# DistributedVisionSchematicPage1_33.net
KiCad netlist of a schematic drawn in EAGLE
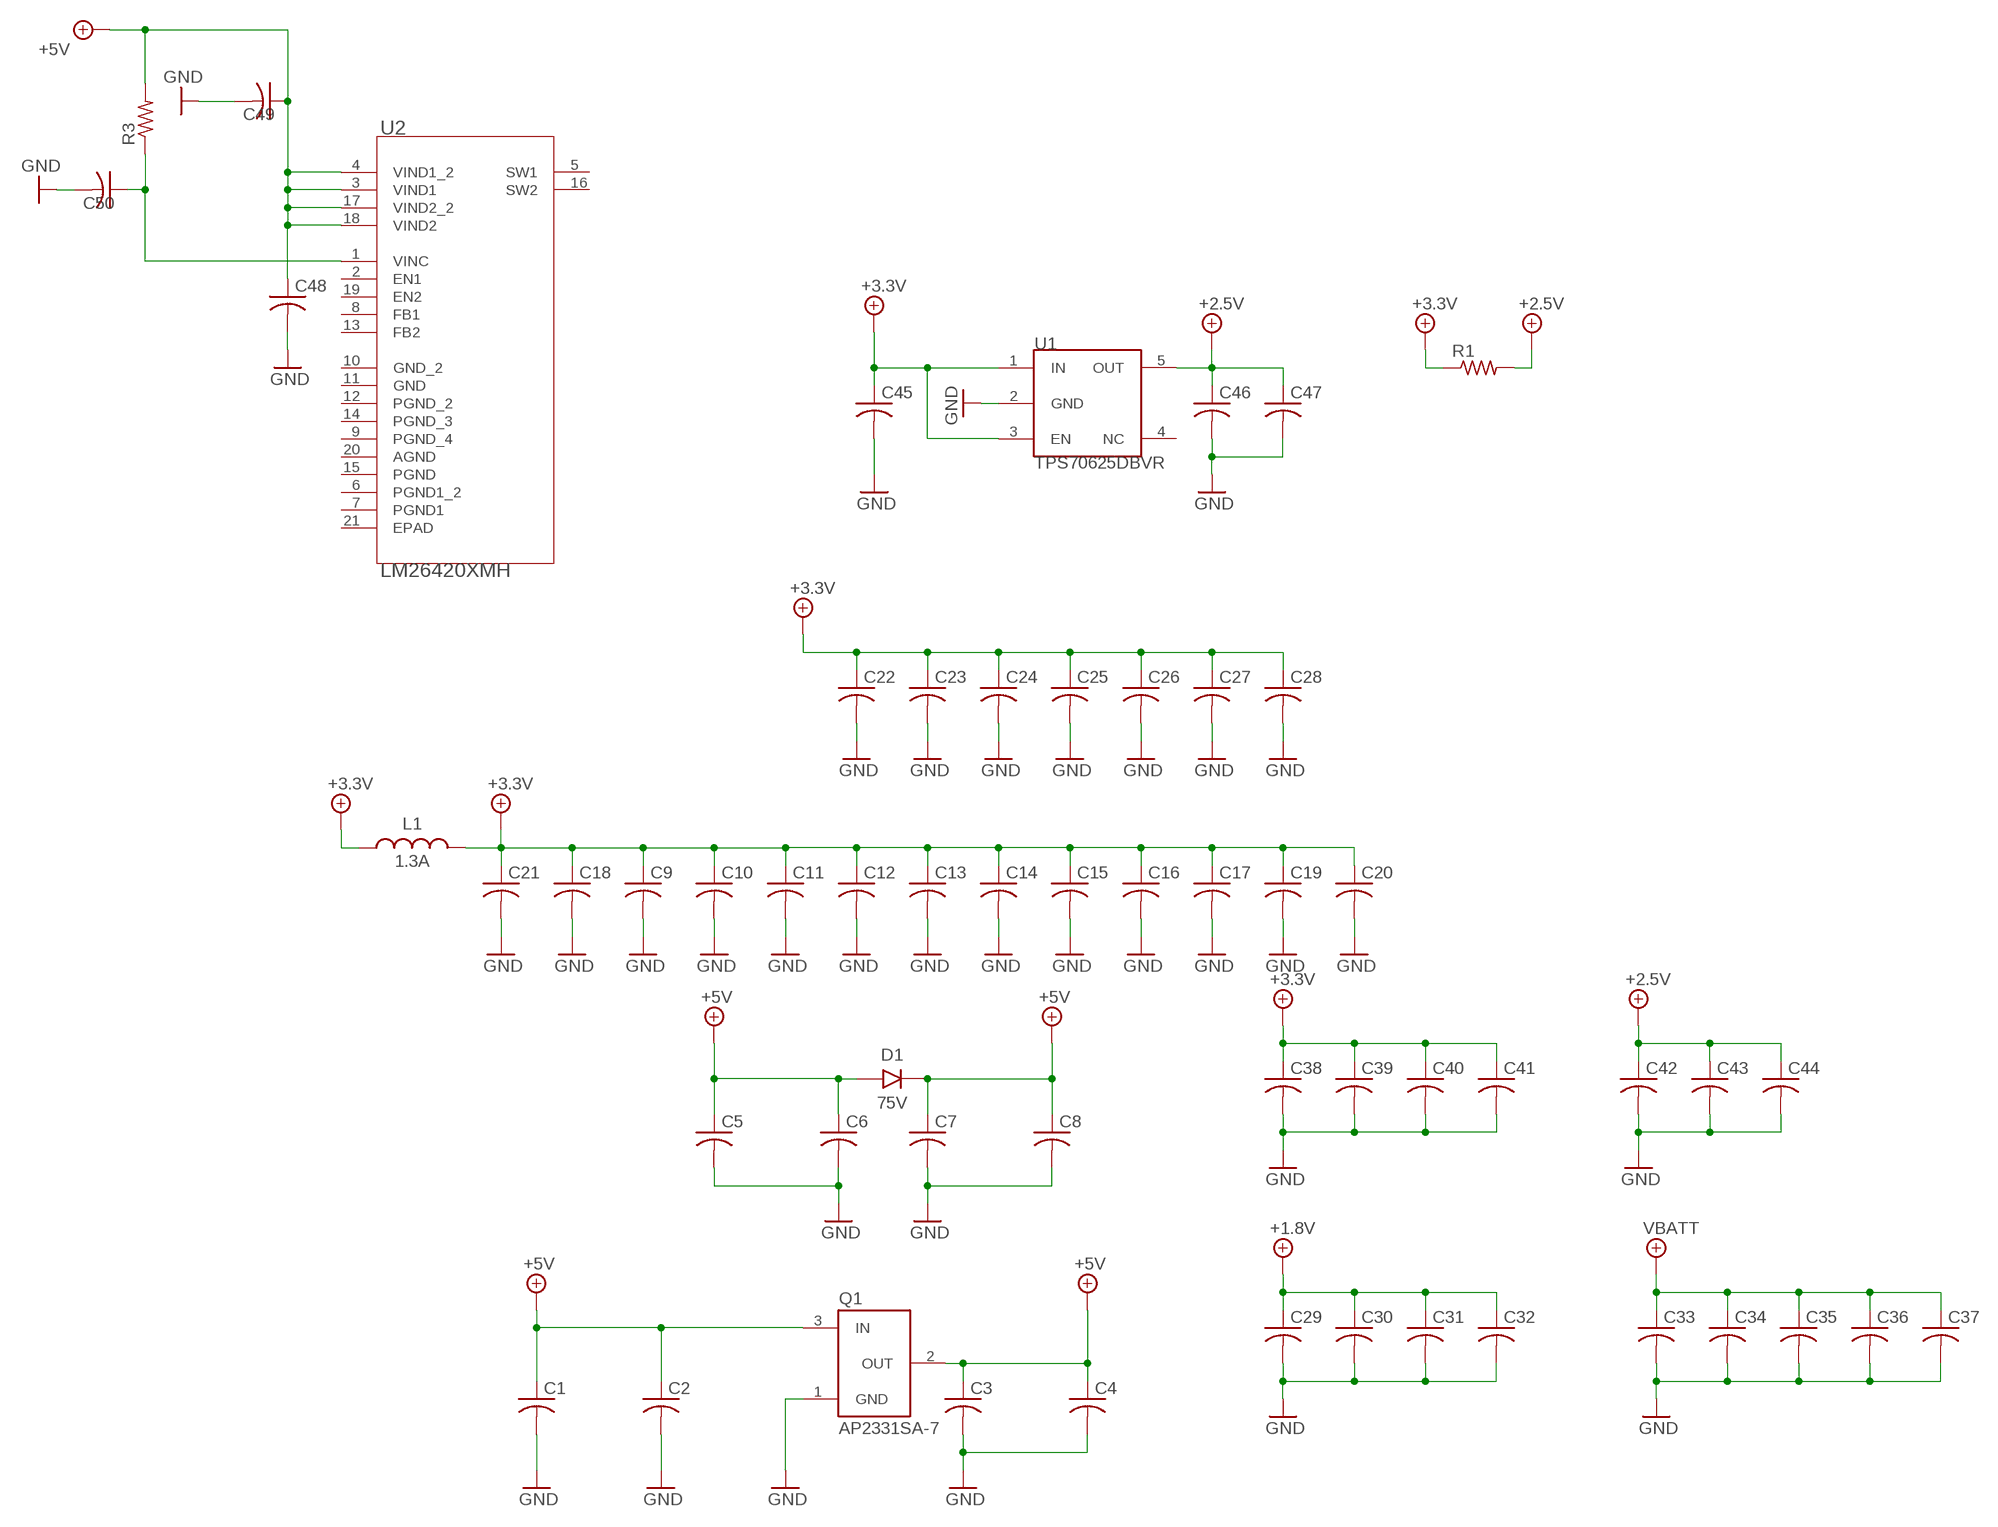
[diagram p0: schematic, sheet 1]

(export (version "E")
  (design (tool "Eeschema 10.0.6"))
  (components
    (comp (ref "C1")
      (value "C-USC0603")
      (footprint "eagle-import:C0603")
      (libsource (lib "eagle-import") (part "C-USC0603"))
    )
    (comp (ref "C2")
      (value "C-USC0603")
      (footprint "eagle-import:C0603")
      (libsource (lib "eagle-import") (part "C-USC0603"))
    )
    (comp (ref "C3")
      (value "C-USC0603")
      (footprint "eagle-import:C0603")
      (libsource (lib "eagle-import") (part "C-USC0603"))
    )
    (comp (ref "C4")
      (value "C-USC0603")
      (footprint "eagle-import:C0603")
      (libsource (lib "eagle-import") (part "C-USC0603"))
    )
    (comp (ref "C5")
      (value "C-USC0603")
      (footprint "eagle-import:C0603")
      (libsource (lib "eagle-import") (part "C-USC0603"))
    )
    (comp (ref "C6")
      (value "C-USC0603")
      (footprint "eagle-import:C0603")
      (libsource (lib "eagle-import") (part "C-USC0603"))
    )
    (comp (ref "C7")
      (value "C-USC0603")
      (footprint "eagle-import:C0603")
      (libsource (lib "eagle-import") (part "C-USC0603"))
    )
    (comp (ref "C8")
      (value "C-USC0603")
      (footprint "eagle-import:C0603")
      (libsource (lib "eagle-import") (part "C-USC0603"))
    )
    (comp (ref "C9")
      (value "C-USC0603")
      (footprint "eagle-import:C0603")
      (libsource (lib "eagle-import") (part "C-USC0603"))
    )
    (comp (ref "C10")
      (value "C-USC0603")
      (footprint "eagle-import:C0603")
      (libsource (lib "eagle-import") (part "C-USC0603"))
    )
    (comp (ref "C11")
      (value "C-USC0603")
      (footprint "eagle-import:C0603")
      (libsource (lib "eagle-import") (part "C-USC0603"))
    )
    (comp (ref "C12")
      (value "C-USC0603")
      (footprint "eagle-import:C0603")
      (libsource (lib "eagle-import") (part "C-USC0603"))
    )
    (comp (ref "C13")
      (value "C-USC0603")
      (footprint "eagle-import:C0603")
      (libsource (lib "eagle-import") (part "C-USC0603"))
    )
    (comp (ref "C14")
      (value "C-USC0603")
      (footprint "eagle-import:C0603")
      (libsource (lib "eagle-import") (part "C-USC0603"))
    )
    (comp (ref "C15")
      (value "C-USC0603")
      (footprint "eagle-import:C0603")
      (libsource (lib "eagle-import") (part "C-USC0603"))
    )
    (comp (ref "C16")
      (value "C-USC0603")
      (footprint "eagle-import:C0603")
      (libsource (lib "eagle-import") (part "C-USC0603"))
    )
    (comp (ref "C17")
      (value "C-USC0603")
      (footprint "eagle-import:C0603")
      (libsource (lib "eagle-import") (part "C-USC0603"))
    )
    (comp (ref "C18")
      (value "C-USC0603")
      (footprint "eagle-import:C0603")
      (libsource (lib "eagle-import") (part "C-USC0603"))
    )
    (comp (ref "C19")
      (value "C-USC0603")
      (footprint "eagle-import:C0603")
      (libsource (lib "eagle-import") (part "C-USC0603"))
    )
    (comp (ref "C20")
      (value "C-USC0603")
      (footprint "eagle-import:C0603")
      (libsource (lib "eagle-import") (part "C-USC0603"))
    )
    (comp (ref "C21")
      (value "C-USC0603")
      (footprint "eagle-import:C0603")
      (libsource (lib "eagle-import") (part "C-USC0603"))
    )
    (comp (ref "C22")
      (value "C-USC0603")
      (footprint "eagle-import:C0603")
      (libsource (lib "eagle-import") (part "C-USC0603"))
    )
    (comp (ref "C23")
      (value "C-USC0603")
      (footprint "eagle-import:C0603")
      (libsource (lib "eagle-import") (part "C-USC0603"))
    )
    (comp (ref "C24")
      (value "C-USC0603")
      (footprint "eagle-import:C0603")
      (libsource (lib "eagle-import") (part "C-USC0603"))
    )
    (comp (ref "C25")
      (value "C-USC0603")
      (footprint "eagle-import:C0603")
      (libsource (lib "eagle-import") (part "C-USC0603"))
    )
    (comp (ref "C26")
      (value "C-USC0603")
      (footprint "eagle-import:C0603")
      (libsource (lib "eagle-import") (part "C-USC0603"))
    )
    (comp (ref "C27")
      (value "C-USC0603")
      (footprint "eagle-import:C0603")
      (libsource (lib "eagle-import") (part "C-USC0603"))
    )
    (comp (ref "C28")
      (value "C-USC0603")
      (footprint "eagle-import:C0603")
      (libsource (lib "eagle-import") (part "C-USC0603"))
    )
    (comp (ref "C29")
      (value "C-USC0603")
      (footprint "eagle-import:C0603")
      (libsource (lib "eagle-import") (part "C-USC0603"))
    )
    (comp (ref "C30")
      (value "C-USC0603")
      (footprint "eagle-import:C0603")
      (libsource (lib "eagle-import") (part "C-USC0603"))
    )
    (comp (ref "C31")
      (value "C-USC0603")
      (footprint "eagle-import:C0603")
      (libsource (lib "eagle-import") (part "C-USC0603"))
    )
    (comp (ref "C32")
      (value "C-USC0603")
      (footprint "eagle-import:C0603")
      (libsource (lib "eagle-import") (part "C-USC0603"))
    )
    (comp (ref "C33")
      (value "C-USC0603")
      (footprint "eagle-import:C0603")
      (libsource (lib "eagle-import") (part "C-USC0603"))
    )
    (comp (ref "C34")
      (value "C-USC0603")
      (footprint "eagle-import:C0603")
      (libsource (lib "eagle-import") (part "C-USC0603"))
    )
    (comp (ref "C35")
      (value "C-USC0603")
      (footprint "eagle-import:C0603")
      (libsource (lib "eagle-import") (part "C-USC0603"))
    )
    (comp (ref "C36")
      (value "C-USC0603")
      (footprint "eagle-import:C0603")
      (libsource (lib "eagle-import") (part "C-USC0603"))
    )
    (comp (ref "C37")
      (value "C-USC0603")
      (footprint "eagle-import:C0603")
      (libsource (lib "eagle-import") (part "C-USC0603"))
    )
    (comp (ref "C38")
      (value "C-USC0603")
      (footprint "eagle-import:C0603")
      (libsource (lib "eagle-import") (part "C-USC0603"))
    )
    (comp (ref "C39")
      (value "C-USC0603")
      (footprint "eagle-import:C0603")
      (libsource (lib "eagle-import") (part "C-USC0603"))
    )
    (comp (ref "C40")
      (value "C-USC0603")
      (footprint "eagle-import:C0603")
      (libsource (lib "eagle-import") (part "C-USC0603"))
    )
    (comp (ref "C41")
      (value "C-USC0603")
      (footprint "eagle-import:C0603")
      (libsource (lib "eagle-import") (part "C-USC0603"))
    )
    (comp (ref "C42")
      (value "C-USC0603")
      (footprint "eagle-import:C0603")
      (libsource (lib "eagle-import") (part "C-USC0603"))
    )
    (comp (ref "C43")
      (value "C-USC0603")
      (footprint "eagle-import:C0603")
      (libsource (lib "eagle-import") (part "C-USC0603"))
    )
    (comp (ref "C44")
      (value "C-USC0603")
      (footprint "eagle-import:C0603")
      (libsource (lib "eagle-import") (part "C-USC0603"))
    )
    (comp (ref "C45")
      (value "C-USC0603")
      (footprint "eagle-import:C0603")
      (libsource (lib "eagle-import") (part "C-USC0603"))
    )
    (comp (ref "C46")
      (value "C-USC0603")
      (footprint "eagle-import:C0603")
      (libsource (lib "eagle-import") (part "C-USC0603"))
    )
    (comp (ref "C47")
      (value "C-USC0603")
      (footprint "eagle-import:C0603")
      (libsource (lib "eagle-import") (part "C-USC0603"))
    )
    (comp (ref "C48")
      (value "C-USC0603")
      (footprint "eagle-import:C0603")
      (libsource (lib "eagle-import") (part "C-USC0603"))
    )
    (comp (ref "C49")
      (value "C-USC0603")
      (footprint "eagle-import:C0603")
      (libsource (lib "eagle-import") (part "C-USC0603"))
    )
    (comp (ref "C50")
      (value "C-USC0603")
      (footprint "eagle-import:C0603")
      (libsource (lib "eagle-import") (part "C-USC0603"))
    )
    (comp (ref "D1")
      (value "75V")
      (footprint "eagle-import:SOD-323")
      (libsource (lib "eagle-import") (part "1N4148WX"))
    )
    (comp (ref "L1")
      (value "1.3A")
      (footprint "eagle-import:0805")
      (libsource (lib "eagle-import") (part "INDUCTOR_0805"))
    )
    (comp (ref "Q1")
      (value "AP2331SA-7")
      (footprint "eagle-import:SOT23")
      (libsource (lib "eagle-import") (part "AP2331SA-7"))
    )
    (comp (ref "R1")
      (value "R-US_R0603")
      (footprint "eagle-import:R0603")
      (libsource (lib "eagle-import") (part "R-US_R0603"))
    )
    (comp (ref "R3")
      (value "R-US_R0603")
      (footprint "eagle-import:R0603")
      (libsource (lib "eagle-import") (part "R-US_R0603"))
    )
    (comp (ref "U1")
      (value "TPS70625DBVR")
      (footprint "eagle-import:DBV0005A")
      (libsource (lib "eagle-import") (part "TPS70625DBVR"))
    )
    (comp (ref "U2")
      (value "LM26420XMH")
      (footprint "eagle-import:PWP0020A")
      (libsource (lib "eagle-import") (part "LM26420XMH"))
    )
  )
  (nets
    (net (code "1") (name "+1.8V") (class "Default")
      (node (ref "C29") (pin "1") (pinfunction "1_1") (pintype "passive"))
      (node (ref "C30") (pin "1") (pinfunction "1_1") (pintype "passive"))
      (node (ref "C31") (pin "1") (pinfunction "1_1") (pintype "passive"))
      (node (ref "C32") (pin "1") (pinfunction "1_1") (pintype "passive"))
    )
    (net (code "2") (name "+2.5V") (class "Default")
      (node (ref "C42") (pin "1") (pinfunction "1_1") (pintype "passive"))
      (node (ref "C43") (pin "1") (pinfunction "1_1") (pintype "passive"))
      (node (ref "C44") (pin "1") (pinfunction "1_1") (pintype "passive"))
      (node (ref "C46") (pin "1") (pinfunction "1_1") (pintype "passive"))
      (node (ref "C47") (pin "1") (pinfunction "1_1") (pintype "passive"))
      (node (ref "R1") (pin "2") (pinfunction "2_2") (pintype "passive"))
      (node (ref "U1") (pin "5") (pinfunction "OUT_5") (pintype "output"))
    )
    (net (code "3") (name "+3.3V") (class "Default")
      (node (ref "C10") (pin "1") (pinfunction "1_1") (pintype "passive"))
      (node (ref "C11") (pin "1") (pinfunction "1_1") (pintype "passive"))
      (node (ref "C12") (pin "1") (pinfunction "1_1") (pintype "passive"))
      (node (ref "C13") (pin "1") (pinfunction "1_1") (pintype "passive"))
      (node (ref "C14") (pin "1") (pinfunction "1_1") (pintype "passive"))
      (node (ref "C15") (pin "1") (pinfunction "1_1") (pintype "passive"))
      (node (ref "C16") (pin "1") (pinfunction "1_1") (pintype "passive"))
      (node (ref "C17") (pin "1") (pinfunction "1_1") (pintype "passive"))
      (node (ref "C18") (pin "1") (pinfunction "1_1") (pintype "passive"))
      (node (ref "C19") (pin "1") (pinfunction "1_1") (pintype "passive"))
      (node (ref "C20") (pin "1") (pinfunction "1_1") (pintype "passive"))
      (node (ref "C21") (pin "1") (pinfunction "1_1") (pintype "passive"))
      (node (ref "C22") (pin "1") (pinfunction "1_1") (pintype "passive"))
      (node (ref "C23") (pin "1") (pinfunction "1_1") (pintype "passive"))
      (node (ref "C24") (pin "1") (pinfunction "1_1") (pintype "passive"))
      (node (ref "C25") (pin "1") (pinfunction "1_1") (pintype "passive"))
      (node (ref "C26") (pin "1") (pinfunction "1_1") (pintype "passive"))
      (node (ref "C27") (pin "1") (pinfunction "1_1") (pintype "passive"))
      (node (ref "C28") (pin "1") (pinfunction "1_1") (pintype "passive"))
      (node (ref "C38") (pin "1") (pinfunction "1_1") (pintype "passive"))
      (node (ref "C39") (pin "1") (pinfunction "1_1") (pintype "passive"))
      (node (ref "C40") (pin "1") (pinfunction "1_1") (pintype "passive"))
      (node (ref "C41") (pin "1") (pinfunction "1_1") (pintype "passive"))
      (node (ref "C45") (pin "1") (pinfunction "1_1") (pintype "passive"))
      (node (ref "C9") (pin "1") (pinfunction "1_1") (pintype "passive"))
      (node (ref "L1") (pin "1") (pinfunction "1_1") (pintype "passive"))
      (node (ref "L1") (pin "2") (pinfunction "2_2") (pintype "passive"))
      (node (ref "R1") (pin "1") (pinfunction "1_1") (pintype "passive"))
      (node (ref "U1") (pin "1") (pinfunction "IN_1") (pintype "input"))
      (node (ref "U1") (pin "3") (pinfunction "EN_3") (pintype "bidirectional"))
    )
    (net (code "4") (name "+5V") (class "Default")
      (node (ref "C1") (pin "1") (pinfunction "1_1") (pintype "passive"))
      (node (ref "C2") (pin "1") (pinfunction "1_1") (pintype "passive"))
      (node (ref "C3") (pin "1") (pinfunction "1_1") (pintype "passive"))
      (node (ref "C4") (pin "1") (pinfunction "1_1") (pintype "passive"))
      (node (ref "C48") (pin "1") (pinfunction "1_1") (pintype "passive"))
      (node (ref "C49") (pin "1") (pinfunction "1_1") (pintype "passive"))
      (node (ref "C5") (pin "1") (pinfunction "1_1") (pintype "passive"))
      (node (ref "C6") (pin "1") (pinfunction "1_1") (pintype "passive"))
      (node (ref "C7") (pin "1") (pinfunction "1_1") (pintype "passive"))
      (node (ref "C8") (pin "1") (pinfunction "1_1") (pintype "passive"))
      (node (ref "D1") (pin "A") (pinfunction "A_A") (pintype "passive"))
      (node (ref "D1") (pin "C") (pinfunction "C_C") (pintype "passive"))
      (node (ref "Q1") (pin "2") (pinfunction "OUT_2") (pintype "bidirectional"))
      (node (ref "Q1") (pin "3") (pinfunction "IN_3") (pintype "bidirectional"))
      (node (ref "R3") (pin "2") (pinfunction "2_2") (pintype "passive"))
      (node (ref "U2") (pin "17") (pinfunction "VIND2_2_17") (pintype "power_in"))
      (node (ref "U2") (pin "18") (pinfunction "VIND2_18") (pintype "power_in"))
      (node (ref "U2") (pin "3") (pinfunction "VIND1_3") (pintype "power_in"))
      (node (ref "U2") (pin "4") (pinfunction "VIND1_2_4") (pintype "power_in"))
    )
    (net (code "5") (name "GND") (class "Default")
      (node (ref "C1") (pin "2") (pinfunction "2_2") (pintype "passive"))
      (node (ref "C10") (pin "2") (pinfunction "2_2") (pintype "passive"))
      (node (ref "C11") (pin "2") (pinfunction "2_2") (pintype "passive"))
      (node (ref "C12") (pin "2") (pinfunction "2_2") (pintype "passive"))
      (node (ref "C13") (pin "2") (pinfunction "2_2") (pintype "passive"))
      (node (ref "C14") (pin "2") (pinfunction "2_2") (pintype "passive"))
      (node (ref "C15") (pin "2") (pinfunction "2_2") (pintype "passive"))
      (node (ref "C16") (pin "2") (pinfunction "2_2") (pintype "passive"))
      (node (ref "C17") (pin "2") (pinfunction "2_2") (pintype "passive"))
      (node (ref "C18") (pin "2") (pinfunction "2_2") (pintype "passive"))
      (node (ref "C19") (pin "2") (pinfunction "2_2") (pintype "passive"))
      (node (ref "C2") (pin "2") (pinfunction "2_2") (pintype "passive"))
      (node (ref "C20") (pin "2") (pinfunction "2_2") (pintype "passive"))
      (node (ref "C21") (pin "2") (pinfunction "2_2") (pintype "passive"))
      (node (ref "C22") (pin "2") (pinfunction "2_2") (pintype "passive"))
      (node (ref "C23") (pin "2") (pinfunction "2_2") (pintype "passive"))
      (node (ref "C24") (pin "2") (pinfunction "2_2") (pintype "passive"))
      (node (ref "C25") (pin "2") (pinfunction "2_2") (pintype "passive"))
      (node (ref "C26") (pin "2") (pinfunction "2_2") (pintype "passive"))
      (node (ref "C27") (pin "2") (pinfunction "2_2") (pintype "passive"))
      (node (ref "C28") (pin "2") (pinfunction "2_2") (pintype "passive"))
      (node (ref "C29") (pin "2") (pinfunction "2_2") (pintype "passive"))
      (node (ref "C3") (pin "2") (pinfunction "2_2") (pintype "passive"))
      (node (ref "C30") (pin "2") (pinfunction "2_2") (pintype "passive"))
      (node (ref "C31") (pin "2") (pinfunction "2_2") (pintype "passive"))
      (node (ref "C32") (pin "2") (pinfunction "2_2") (pintype "passive"))
      (node (ref "C33") (pin "2") (pinfunction "2_2") (pintype "passive"))
      (node (ref "C34") (pin "2") (pinfunction "2_2") (pintype "passive"))
      (node (ref "C35") (pin "2") (pinfunction "2_2") (pintype "passive"))
      (node (ref "C36") (pin "2") (pinfunction "2_2") (pintype "passive"))
      (node (ref "C37") (pin "2") (pinfunction "2_2") (pintype "passive"))
      (node (ref "C38") (pin "2") (pinfunction "2_2") (pintype "passive"))
      (node (ref "C39") (pin "2") (pinfunction "2_2") (pintype "passive"))
      (node (ref "C4") (pin "2") (pinfunction "2_2") (pintype "passive"))
      (node (ref "C40") (pin "2") (pinfunction "2_2") (pintype "passive"))
      (node (ref "C41") (pin "2") (pinfunction "2_2") (pintype "passive"))
      (node (ref "C42") (pin "2") (pinfunction "2_2") (pintype "passive"))
      (node (ref "C43") (pin "2") (pinfunction "2_2") (pintype "passive"))
      (node (ref "C44") (pin "2") (pinfunction "2_2") (pintype "passive"))
      (node (ref "C45") (pin "2") (pinfunction "2_2") (pintype "passive"))
      (node (ref "C46") (pin "2") (pinfunction "2_2") (pintype "passive"))
      (node (ref "C47") (pin "2") (pinfunction "2_2") (pintype "passive"))
      (node (ref "C48") (pin "2") (pinfunction "2_2") (pintype "passive"))
      (node (ref "C49") (pin "2") (pinfunction "2_2") (pintype "passive"))
      (node (ref "C5") (pin "2") (pinfunction "2_2") (pintype "passive"))
      (node (ref "C50") (pin "2") (pinfunction "2_2") (pintype "passive"))
      (node (ref "C6") (pin "2") (pinfunction "2_2") (pintype "passive"))
      (node (ref "C7") (pin "2") (pinfunction "2_2") (pintype "passive"))
      (node (ref "C8") (pin "2") (pinfunction "2_2") (pintype "passive"))
      (node (ref "C9") (pin "2") (pinfunction "2_2") (pintype "passive"))
      (node (ref "Q1") (pin "1") (pinfunction "GND_1") (pintype "bidirectional"))
      (node (ref "U1") (pin "2") (pinfunction "GND_2") (pintype "power_in"))
    )
    (net (code "6") (name "Net-(U2-VINC)") (class "Default")
      (node (ref "C50") (pin "1") (pinfunction "1_1") (pintype "passive"))
      (node (ref "R3") (pin "1") (pinfunction "1_1") (pintype "passive"))
      (node (ref "U2") (pin "1") (pinfunction "VINC_1") (pintype "power_in"))
    )
    (net (code "7") (name "VBATT") (class "Default")
      (node (ref "C33") (pin "1") (pinfunction "1_1") (pintype "passive"))
      (node (ref "C34") (pin "1") (pinfunction "1_1") (pintype "passive"))
      (node (ref "C35") (pin "1") (pinfunction "1_1") (pintype "passive"))
      (node (ref "C36") (pin "1") (pinfunction "1_1") (pintype "passive"))
      (node (ref "C37") (pin "1") (pinfunction "1_1") (pintype "passive"))
    )
    (net (code "8") (name "unconnected-(U1-NC-Pad4)") (class "Default")
      (node (ref "U1") (pin "4") (pinfunction "NC_4") (pintype "no_connect"))
    )
    (net (code "9") (name "unconnected-(U2-AGND-Pad20)") (class "Default")
      (node (ref "U2") (pin "20") (pinfunction "AGND_20") (pintype "passive"))
    )
    (net (code "10") (name "unconnected-(U2-EN1-Pad2)") (class "Default")
      (node (ref "U2") (pin "2") (pinfunction "EN1_2") (pintype "input"))
    )
    (net (code "11") (name "unconnected-(U2-EN2-Pad19)") (class "Default")
      (node (ref "U2") (pin "19") (pinfunction "EN2_19") (pintype "input"))
    )
    (net (code "12") (name "unconnected-(U2-EPAD-Pad21)") (class "Default")
      (node (ref "U2") (pin "21") (pinfunction "EPAD_21") (pintype "passive"))
    )
    (net (code "13") (name "unconnected-(U2-FB1-Pad8)") (class "Default")
      (node (ref "U2") (pin "8") (pinfunction "FB1_8") (pintype "input"))
    )
    (net (code "14") (name "unconnected-(U2-FB2-Pad13)") (class "Default")
      (node (ref "U2") (pin "13") (pinfunction "FB2_13") (pintype "input"))
    )
    (net (code "15") (name "unconnected-(U2-GND-Pad11)") (class "Default")
      (node (ref "U2") (pin "11") (pinfunction "GND_11") (pintype "passive"))
    )
    (net (code "16") (name "unconnected-(U2-GND_2-Pad10)") (class "Default")
      (node (ref "U2") (pin "10") (pinfunction "GND_2_10") (pintype "passive"))
    )
    (net (code "17") (name "unconnected-(U2-PGND-Pad15)") (class "Default")
      (node (ref "U2") (pin "15") (pinfunction "PGND_15") (pintype "passive"))
    )
    (net (code "18") (name "unconnected-(U2-PGND1-Pad7)") (class "Default")
      (node (ref "U2") (pin "7") (pinfunction "PGND1_7") (pintype "passive"))
    )
    (net (code "19") (name "unconnected-(U2-PGND1_2-Pad6)") (class "Default")
      (node (ref "U2") (pin "6") (pinfunction "PGND1_2_6") (pintype "passive"))
    )
    (net (code "20") (name "unconnected-(U2-PGND_2-Pad12)") (class "Default")
      (node (ref "U2") (pin "12") (pinfunction "PGND_2_12") (pintype "passive"))
    )
    (net (code "21") (name "unconnected-(U2-PGND_3-Pad14)") (class "Default")
      (node (ref "U2") (pin "14") (pinfunction "PGND_3_14") (pintype "passive"))
    )
    (net (code "22") (name "unconnected-(U2-PGND_4-Pad9)") (class "Default")
      (node (ref "U2") (pin "9") (pinfunction "PGND_4_9") (pintype "passive"))
    )
    (net (code "23") (name "unconnected-(U2-SW1-Pad5)") (class "Default")
      (node (ref "U2") (pin "5") (pinfunction "SW1_5") (pintype "output"))
    )
    (net (code "24") (name "unconnected-(U2-SW2-Pad16)") (class "Default")
      (node (ref "U2") (pin "16") (pinfunction "SW2_16") (pintype "output"))
    )
  )
)
